# Genesis_-_Multitap.net
KiCad netlist of a schematic drawn in EAGLE
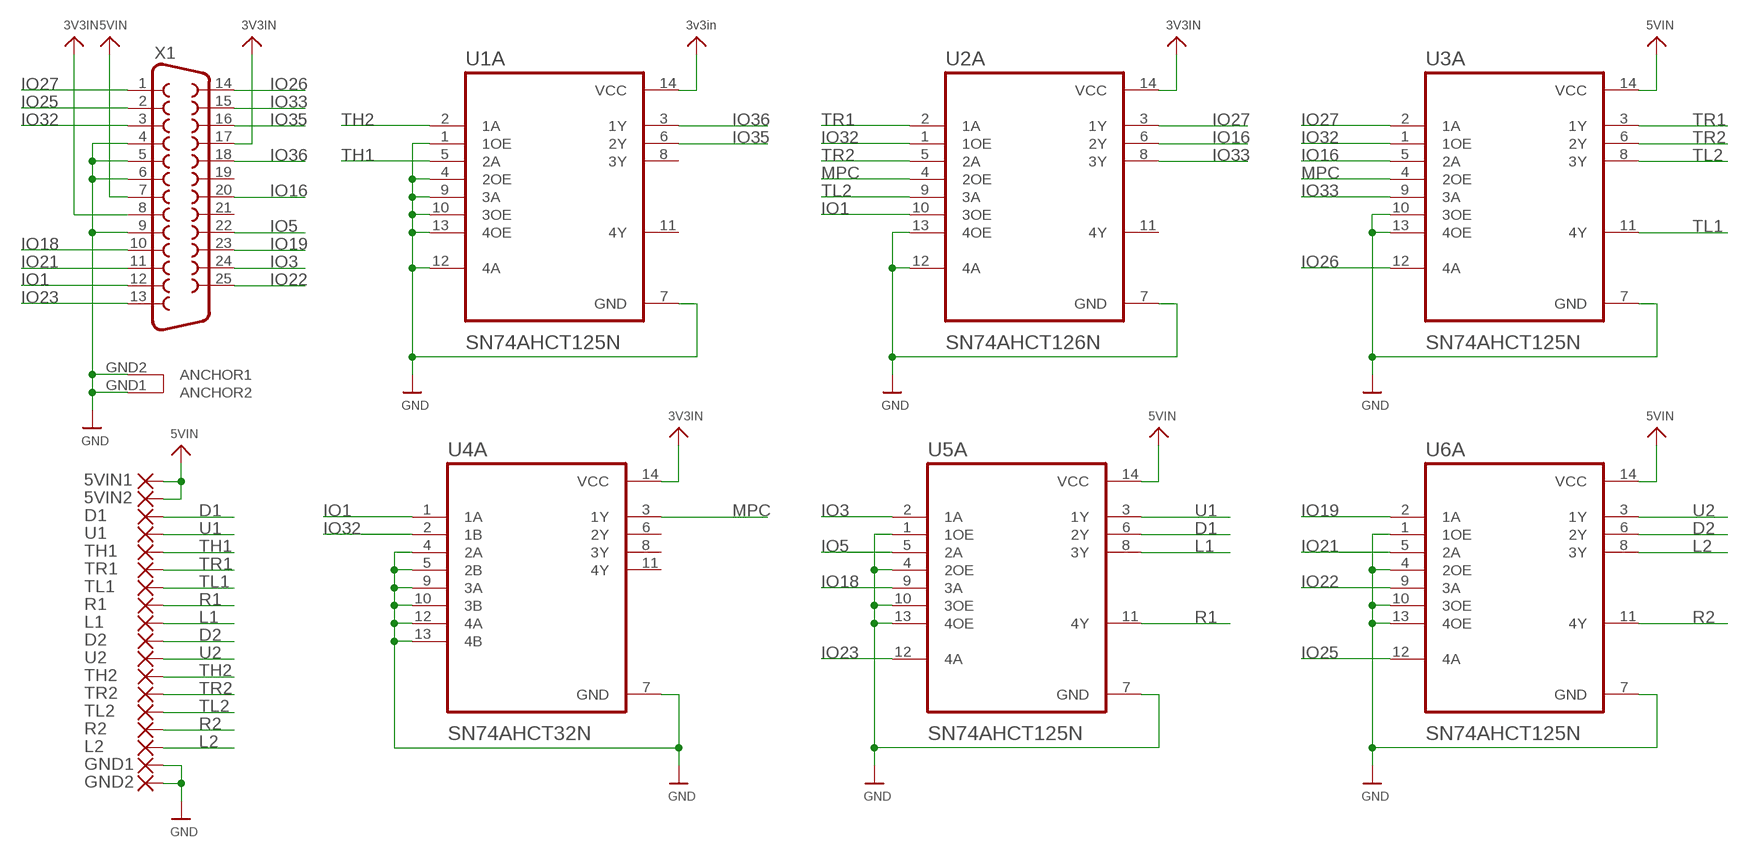
[diagram p0: schematic, sheet 1]

(export (version "E")
  (design (tool "Eeschema 10.0.6"))
  (components
    (comp (ref "5VIN1")
      (value "SMD5")
      (footprint "eagle-import:SMD2,54-5,08")
      (libsource (lib "eagle-import") (part "SMD5"))
    )
    (comp (ref "5VIN2")
      (value "SMD5")
      (footprint "eagle-import:SMD2,54-5,08")
      (libsource (lib "eagle-import") (part "SMD5"))
    )
    (comp (ref "D1")
      (value "SMD5")
      (footprint "eagle-import:SMD2,54-5,08")
      (libsource (lib "eagle-import") (part "SMD5"))
    )
    (comp (ref "D2")
      (value "SMD5")
      (footprint "eagle-import:SMD2,54-5,08")
      (libsource (lib "eagle-import") (part "SMD5"))
    )
    (comp (ref "GND1")
      (value "SMD5")
      (footprint "eagle-import:SMD2,54-5,08")
      (libsource (lib "eagle-import") (part "SMD5"))
    )
    (comp (ref "GND2")
      (value "SMD5")
      (footprint "eagle-import:SMD2,54-5,08")
      (libsource (lib "eagle-import") (part "SMD5"))
    )
    (comp (ref "L1")
      (value "SMD5")
      (footprint "eagle-import:SMD2,54-5,08")
      (libsource (lib "eagle-import") (part "SMD5"))
    )
    (comp (ref "L2")
      (value "SMD5")
      (footprint "eagle-import:SMD2,54-5,08")
      (libsource (lib "eagle-import") (part "SMD5"))
    )
    (comp (ref "R1")
      (value "SMD5")
      (footprint "eagle-import:SMD2,54-5,08")
      (libsource (lib "eagle-import") (part "SMD5"))
    )
    (comp (ref "R2")
      (value "SMD5")
      (footprint "eagle-import:SMD2,54-5,08")
      (libsource (lib "eagle-import") (part "SMD5"))
    )
    (comp (ref "TH1")
      (value "SMD5")
      (footprint "eagle-import:SMD2,54-5,08")
      (libsource (lib "eagle-import") (part "SMD5"))
    )
    (comp (ref "TH2")
      (value "SMD5")
      (footprint "eagle-import:SMD2,54-5,08")
      (libsource (lib "eagle-import") (part "SMD5"))
    )
    (comp (ref "TL1")
      (value "SMD5")
      (footprint "eagle-import:SMD2,54-5,08")
      (libsource (lib "eagle-import") (part "SMD5"))
    )
    (comp (ref "TL2")
      (value "SMD5")
      (footprint "eagle-import:SMD2,54-5,08")
      (libsource (lib "eagle-import") (part "SMD5"))
    )
    (comp (ref "TR1")
      (value "SMD5")
      (footprint "eagle-import:SMD2,54-5,08")
      (libsource (lib "eagle-import") (part "SMD5"))
    )
    (comp (ref "TR2")
      (value "SMD5")
      (footprint "eagle-import:SMD2,54-5,08")
      (libsource (lib "eagle-import") (part "SMD5"))
    )
    (comp (ref "U1")
      (value "SMD5")
      (footprint "eagle-import:SMD2,54-5,08")
      (libsource (lib "eagle-import") (part "SMD5"))
    )
    (comp (ref "U1A")
      (value "SN74AHCT125N")
      (footprint "eagle-import:DIP794W45P254L1969H508Q14")
      (fields (field (name "MF") "Texas Instruments"))
      (libsource (lib "eagle-import") (part "SN74AHCT125N"))
    )
    (comp (ref "U2")
      (value "SMD5")
      (footprint "eagle-import:SMD2,54-5,08")
      (libsource (lib "eagle-import") (part "SMD5"))
    )
    (comp (ref "U2A")
      (value "SN74AHCT126N")
      (footprint "eagle-import:DIP794W45P254L1969H508Q14")
      (fields (field (name "MF") "Texas Instruments") (field (name "MP") "SN74AHCT125N"))
      (libsource (lib "eagle-import") (part "SN74AHCT125N"))
    )
    (comp (ref "U3A")
      (value "SN74AHCT125N")
      (footprint "eagle-import:DIP794W45P254L1969H508Q14")
      (fields (field (name "MF") "Texas Instruments"))
      (libsource (lib "eagle-import") (part "SN74AHCT125N"))
    )
    (comp (ref "U4A")
      (value "SN74AHCT32N")
      (footprint "eagle-import:DIP794W45P254L1969H508Q14")
      (fields
        (field (name "DIGI-KEY_PART_NUMBER") "2156-SN74AHCT32N-ND")
        (field (name "MF") "Texas Instruments")
      )
      (libsource (lib "eagle-import") (part "SN74AHCT32N"))
    )
    (comp (ref "U5A")
      (value "SN74AHCT125N")
      (footprint "eagle-import:DIP794W45P254L1969H508Q14")
      (fields (field (name "MF") "Texas Instruments"))
      (libsource (lib "eagle-import") (part "SN74AHCT125N"))
    )
    (comp (ref "U6A")
      (value "SN74AHCT125N")
      (footprint "eagle-import:DIP794W45P254L1969H508Q14")
      (fields (field (name "MF") "Texas Instruments"))
      (libsource (lib "eagle-import") (part "SN74AHCT125N"))
    )
    (comp (ref "X1")
      (value "DB25_FEMALEHP")
      (footprint "eagle-import:F25HP")
      (libsource (lib "eagle-import") (part "DB25_FEMALEHP"))
    )
  )
  (nets
    (net (code "1") (name "/D1") (class "Default")
      (node (ref "D1") (pin "1") (pinfunction "P_1") (pintype "passive"))
      (node (ref "U5A") (pin "6") (pinfunction "2Y_6") (pintype "output"))
    )
    (net (code "2") (name "/D2") (class "Default")
      (node (ref "D2") (pin "1") (pinfunction "P_1") (pintype "passive"))
      (node (ref "U6A") (pin "6") (pinfunction "2Y_6") (pintype "output"))
    )
    (net (code "3") (name "/IO1") (class "Default")
      (node (ref "U2A") (pin "10") (pinfunction "3OE_10") (pintype "input"))
      (node (ref "U4A") (pin "1") (pinfunction "1A_1") (pintype "input"))
      (node (ref "X1") (pin "12") (pinfunction "12_12") (pintype "passive"))
    )
    (net (code "4") (name "/IO3") (class "Default")
      (node (ref "U5A") (pin "2") (pinfunction "1A_2") (pintype "input"))
      (node (ref "X1") (pin "24") (pinfunction "24_24") (pintype "passive"))
    )
    (net (code "5") (name "/IO5") (class "Default")
      (node (ref "U5A") (pin "5") (pinfunction "2A_5") (pintype "input"))
      (node (ref "X1") (pin "22") (pinfunction "22_22") (pintype "passive"))
    )
    (net (code "6") (name "/IO16") (class "Default")
      (node (ref "U2A") (pin "6") (pinfunction "2Y_6") (pintype "output"))
      (node (ref "U3A") (pin "5") (pinfunction "2A_5") (pintype "input"))
      (node (ref "X1") (pin "20") (pinfunction "20_20") (pintype "passive"))
    )
    (net (code "7") (name "/IO18") (class "Default")
      (node (ref "U5A") (pin "9") (pinfunction "3A_9") (pintype "input"))
      (node (ref "X1") (pin "10") (pinfunction "10_10") (pintype "passive"))
    )
    (net (code "8") (name "/IO19") (class "Default")
      (node (ref "U6A") (pin "2") (pinfunction "1A_2") (pintype "input"))
      (node (ref "X1") (pin "23") (pinfunction "23_23") (pintype "passive"))
    )
    (net (code "9") (name "/IO21") (class "Default")
      (node (ref "U6A") (pin "5") (pinfunction "2A_5") (pintype "input"))
      (node (ref "X1") (pin "11") (pinfunction "11_11") (pintype "passive"))
    )
    (net (code "10") (name "/IO22") (class "Default")
      (node (ref "U6A") (pin "9") (pinfunction "3A_9") (pintype "input"))
      (node (ref "X1") (pin "25") (pinfunction "25_25") (pintype "passive"))
    )
    (net (code "11") (name "/IO23") (class "Default")
      (node (ref "U5A") (pin "12") (pinfunction "4A_12") (pintype "bidirectional"))
      (node (ref "X1") (pin "13") (pinfunction "13_13") (pintype "passive"))
    )
    (net (code "12") (name "/IO25") (class "Default")
      (node (ref "U6A") (pin "12") (pinfunction "4A_12") (pintype "bidirectional"))
      (node (ref "X1") (pin "2") (pinfunction "2_2") (pintype "passive"))
    )
    (net (code "13") (name "/IO26") (class "Default")
      (node (ref "U3A") (pin "12") (pinfunction "4A_12") (pintype "bidirectional"))
      (node (ref "X1") (pin "14") (pinfunction "14_14") (pintype "passive"))
    )
    (net (code "14") (name "/IO27") (class "Default")
      (node (ref "U2A") (pin "3") (pinfunction "1Y_3") (pintype "output"))
      (node (ref "U3A") (pin "2") (pinfunction "1A_2") (pintype "input"))
      (node (ref "X1") (pin "1") (pinfunction "1_1") (pintype "passive"))
    )
    (net (code "15") (name "/IO32") (class "Default")
      (node (ref "U2A") (pin "1") (pinfunction "1OE_1") (pintype "input"))
      (node (ref "U3A") (pin "1") (pinfunction "1OE_1") (pintype "input"))
      (node (ref "U4A") (pin "2") (pinfunction "1B_2") (pintype "input"))
      (node (ref "X1") (pin "3") (pinfunction "3_3") (pintype "passive"))
    )
    (net (code "16") (name "/IO33") (class "Default")
      (node (ref "U2A") (pin "8") (pinfunction "3Y_8") (pintype "output"))
      (node (ref "U3A") (pin "9") (pinfunction "3A_9") (pintype "input"))
      (node (ref "X1") (pin "15") (pinfunction "15_15") (pintype "passive"))
    )
    (net (code "17") (name "/IO35") (class "Default")
      (node (ref "U1A") (pin "6") (pinfunction "2Y_6") (pintype "output"))
      (node (ref "X1") (pin "16") (pinfunction "16_16") (pintype "passive"))
    )
    (net (code "18") (name "/IO36") (class "Default")
      (node (ref "U1A") (pin "3") (pinfunction "1Y_3") (pintype "output"))
      (node (ref "X1") (pin "18") (pinfunction "18_18") (pintype "passive"))
    )
    (net (code "19") (name "/L1") (class "Default")
      (node (ref "L1") (pin "1") (pinfunction "P_1") (pintype "passive"))
      (node (ref "U5A") (pin "8") (pinfunction "3Y_8") (pintype "output"))
    )
    (net (code "20") (name "/L2") (class "Default")
      (node (ref "L2") (pin "1") (pinfunction "P_1") (pintype "passive"))
      (node (ref "U6A") (pin "8") (pinfunction "3Y_8") (pintype "output"))
    )
    (net (code "21") (name "/MPC") (class "Default")
      (node (ref "U2A") (pin "4") (pinfunction "2OE_4") (pintype "input"))
      (node (ref "U3A") (pin "4") (pinfunction "2OE_4") (pintype "input"))
      (node (ref "U4A") (pin "3") (pinfunction "1Y_3") (pintype "output"))
    )
    (net (code "22") (name "/R1") (class "Default")
      (node (ref "R1") (pin "1") (pinfunction "P_1") (pintype "passive"))
      (node (ref "U5A") (pin "11") (pinfunction "4Y_11") (pintype "output"))
    )
    (net (code "23") (name "/R2") (class "Default")
      (node (ref "R2") (pin "1") (pinfunction "P_1") (pintype "passive"))
      (node (ref "U6A") (pin "11") (pinfunction "4Y_11") (pintype "output"))
    )
    (net (code "24") (name "/TH1") (class "Default")
      (node (ref "TH1") (pin "1") (pinfunction "P_1") (pintype "passive"))
      (node (ref "U1A") (pin "5") (pinfunction "2A_5") (pintype "input"))
    )
    (net (code "25") (name "/TH2") (class "Default")
      (node (ref "TH2") (pin "1") (pinfunction "P_1") (pintype "passive"))
      (node (ref "U1A") (pin "2") (pinfunction "1A_2") (pintype "input"))
    )
    (net (code "26") (name "/TL1") (class "Default")
      (node (ref "TL1") (pin "1") (pinfunction "P_1") (pintype "passive"))
      (node (ref "U3A") (pin "11") (pinfunction "4Y_11") (pintype "output"))
    )
    (net (code "27") (name "/TL2") (class "Default")
      (node (ref "TL2") (pin "1") (pinfunction "P_1") (pintype "passive"))
      (node (ref "U2A") (pin "9") (pinfunction "3A_9") (pintype "input"))
      (node (ref "U3A") (pin "8") (pinfunction "3Y_8") (pintype "output"))
    )
    (net (code "28") (name "/TR1") (class "Default")
      (node (ref "TR1") (pin "1") (pinfunction "P_1") (pintype "passive"))
      (node (ref "U2A") (pin "2") (pinfunction "1A_2") (pintype "input"))
      (node (ref "U3A") (pin "3") (pinfunction "1Y_3") (pintype "output"))
    )
    (net (code "29") (name "/TR2") (class "Default")
      (node (ref "TR2") (pin "1") (pinfunction "P_1") (pintype "passive"))
      (node (ref "U2A") (pin "5") (pinfunction "2A_5") (pintype "input"))
      (node (ref "U3A") (pin "6") (pinfunction "2Y_6") (pintype "output"))
    )
    (net (code "30") (name "/U1") (class "Default")
      (node (ref "U1") (pin "1") (pinfunction "P_1") (pintype "passive"))
      (node (ref "U5A") (pin "3") (pinfunction "1Y_3") (pintype "output"))
    )
    (net (code "31") (name "/U2") (class "Default")
      (node (ref "U2") (pin "1") (pinfunction "P_1") (pintype "passive"))
      (node (ref "U6A") (pin "3") (pinfunction "1Y_3") (pintype "output"))
    )
    (net (code "32") (name "3V3IN") (class "Default")
      (node (ref "U1A") (pin "14") (pinfunction "VCC_14") (pintype "power_in"))
      (node (ref "U2A") (pin "14") (pinfunction "VCC_14") (pintype "power_in"))
      (node (ref "U4A") (pin "14") (pinfunction "VCC_14") (pintype "power_in"))
      (node (ref "X1") (pin "17") (pinfunction "17_17") (pintype "passive"))
      (node (ref "X1") (pin "8") (pinfunction "8_8") (pintype "passive"))
    )
    (net (code "33") (name "5VIN") (class "Default")
      (node (ref "5VIN1") (pin "1") (pinfunction "P_1") (pintype "passive"))
      (node (ref "5VIN2") (pin "1") (pinfunction "P_1") (pintype "passive"))
      (node (ref "U3A") (pin "14") (pinfunction "VCC_14") (pintype "power_in"))
      (node (ref "U5A") (pin "14") (pinfunction "VCC_14") (pintype "power_in"))
      (node (ref "U6A") (pin "14") (pinfunction "VCC_14") (pintype "power_in"))
      (node (ref "X1") (pin "7") (pinfunction "7_7") (pintype "passive"))
    )
    (net (code "34") (name "GND") (class "Default")
      (node (ref "GND1") (pin "1") (pinfunction "P_1") (pintype "passive"))
      (node (ref "GND2") (pin "1") (pinfunction "P_1") (pintype "passive"))
      (node (ref "U1A") (pin "1") (pinfunction "1OE_1") (pintype "input"))
      (node (ref "U1A") (pin "10") (pinfunction "3OE_10") (pintype "input"))
      (node (ref "U1A") (pin "12") (pinfunction "4A_12") (pintype "bidirectional"))
      (node (ref "U1A") (pin "13") (pinfunction "4OE_13") (pintype "input"))
      (node (ref "U1A") (pin "4") (pinfunction "2OE_4") (pintype "input"))
      (node (ref "U1A") (pin "7") (pinfunction "GND_7") (pintype "power_in"))
      (node (ref "U1A") (pin "9") (pinfunction "3A_9") (pintype "input"))
      (node (ref "U2A") (pin "12") (pinfunction "4A_12") (pintype "bidirectional"))
      (node (ref "U2A") (pin "13") (pinfunction "4OE_13") (pintype "input"))
      (node (ref "U2A") (pin "7") (pinfunction "GND_7") (pintype "power_in"))
      (node (ref "U3A") (pin "10") (pinfunction "3OE_10") (pintype "input"))
      (node (ref "U3A") (pin "13") (pinfunction "4OE_13") (pintype "input"))
      (node (ref "U3A") (pin "7") (pinfunction "GND_7") (pintype "power_in"))
      (node (ref "U4A") (pin "10") (pinfunction "3B_10") (pintype "input"))
      (node (ref "U4A") (pin "12") (pinfunction "4A_12") (pintype "input"))
      (node (ref "U4A") (pin "13") (pinfunction "4B_13") (pintype "input"))
      (node (ref "U4A") (pin "4") (pinfunction "2A_4") (pintype "input"))
      (node (ref "U4A") (pin "5") (pinfunction "2B_5") (pintype "input"))
      (node (ref "U4A") (pin "7") (pinfunction "GND_7") (pintype "power_in"))
      (node (ref "U4A") (pin "9") (pinfunction "3A_9") (pintype "input"))
      (node (ref "U5A") (pin "1") (pinfunction "1OE_1") (pintype "input"))
      (node (ref "U5A") (pin "10") (pinfunction "3OE_10") (pintype "input"))
      (node (ref "U5A") (pin "13") (pinfunction "4OE_13") (pintype "input"))
      (node (ref "U5A") (pin "4") (pinfunction "2OE_4") (pintype "input"))
      (node (ref "U5A") (pin "7") (pinfunction "GND_7") (pintype "power_in"))
      (node (ref "U6A") (pin "1") (pinfunction "1OE_1") (pintype "input"))
      (node (ref "U6A") (pin "10") (pinfunction "3OE_10") (pintype "input"))
      (node (ref "U6A") (pin "13") (pinfunction "4OE_13") (pintype "input"))
      (node (ref "U6A") (pin "4") (pinfunction "2OE_4") (pintype "input"))
      (node (ref "U6A") (pin "7") (pinfunction "GND_7") (pintype "power_in"))
      (node (ref "X1") (pin "4") (pinfunction "4_4") (pintype "passive"))
      (node (ref "X1") (pin "5") (pinfunction "5_5") (pintype "passive"))
      (node (ref "X1") (pin "6") (pinfunction "6_6") (pintype "passive"))
      (node (ref "X1") (pin "9") (pinfunction "9_9") (pintype "passive"))
      (node (ref "X1") (pin "GND1") (pinfunction "ANCHOR2_GND1") (pintype "bidirectional"))
      (node (ref "X1") (pin "GND2") (pinfunction "ANCHOR1_GND2") (pintype "bidirectional"))
    )
    (net (code "35") (name "unconnected-(U1A-3Y-Pad8)") (class "Default")
      (node (ref "U1A") (pin "8") (pinfunction "3Y_8") (pintype "output"))
    )
    (net (code "36") (name "unconnected-(U1A-4Y-Pad11)") (class "Default")
      (node (ref "U1A") (pin "11") (pinfunction "4Y_11") (pintype "output"))
    )
    (net (code "37") (name "unconnected-(U2A-4Y-Pad11)") (class "Default")
      (node (ref "U2A") (pin "11") (pinfunction "4Y_11") (pintype "output"))
    )
    (net (code "38") (name "unconnected-(U4A-2Y-Pad6)") (class "Default")
      (node (ref "U4A") (pin "6") (pinfunction "2Y_6") (pintype "output"))
    )
    (net (code "39") (name "unconnected-(U4A-3Y-Pad8)") (class "Default")
      (node (ref "U4A") (pin "8") (pinfunction "3Y_8") (pintype "output"))
    )
    (net (code "40") (name "unconnected-(U4A-4Y-Pad11)") (class "Default")
      (node (ref "U4A") (pin "11") (pinfunction "4Y_11") (pintype "output"))
    )
    (net (code "41") (name "unconnected-(X1-Pad19)") (class "Default")
      (node (ref "X1") (pin "19") (pinfunction "19_19") (pintype "passive"))
    )
    (net (code "42") (name "unconnected-(X1-Pad21)") (class "Default")
      (node (ref "X1") (pin "21") (pinfunction "21_21") (pintype "passive"))
    )
  )
)
